# Own_RPi_Streamerboard_pro_v1_4_Final_AR.net
KiCad netlist of a schematic drawn in EAGLE
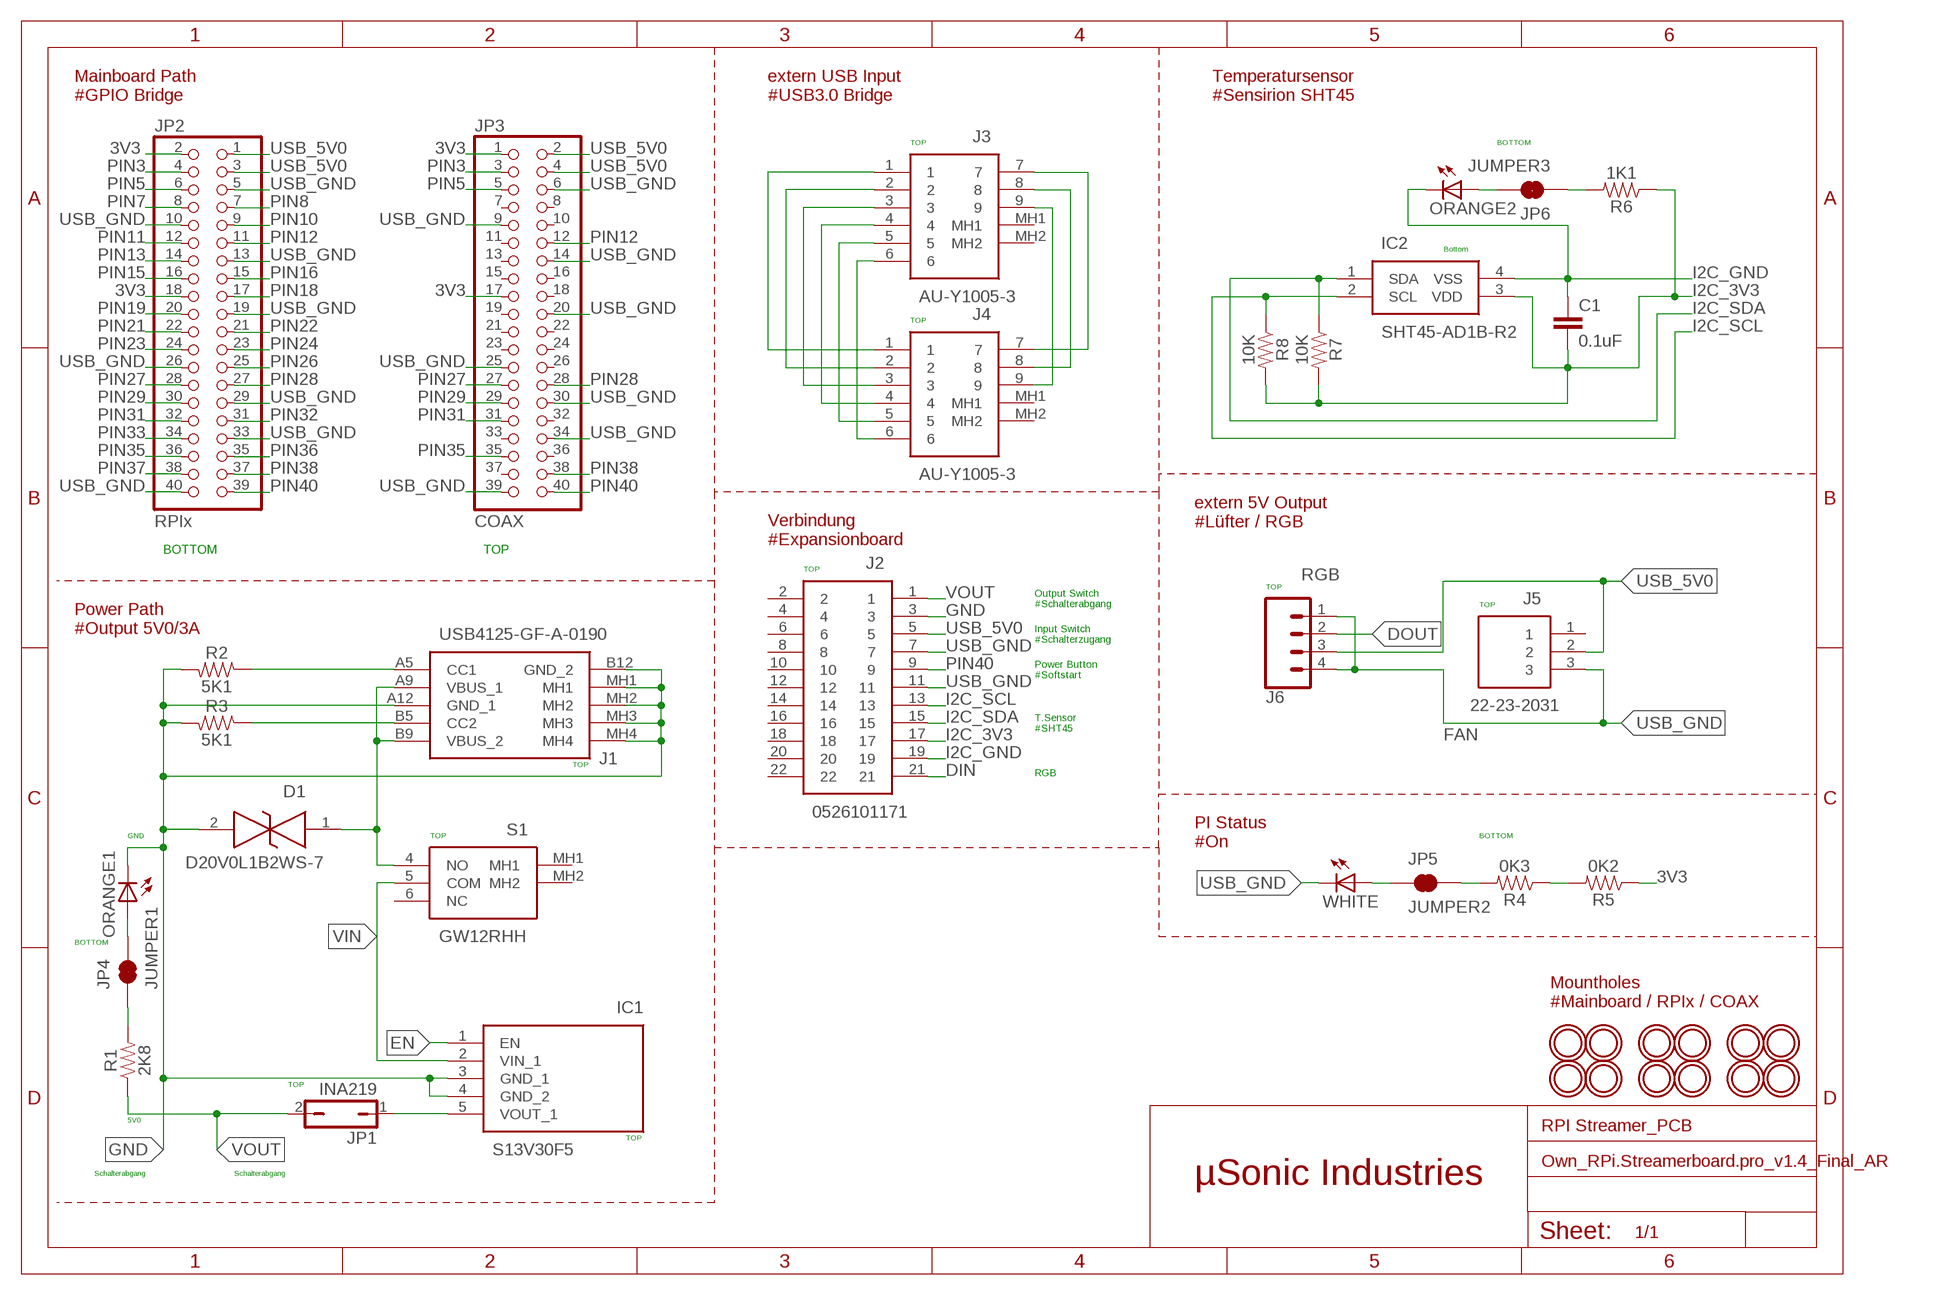
[diagram p0: schematic, sheet 1]

(export (version "E")
  (design (tool "Eeschema 10.0.6"))
  (components
    (comp (ref "C1")
      (value "0.1uF")
      (footprint "eagle-import:0805")
      (libsource (lib "eagle-import") (part "1.0UF-0805-25V-10%"))
    )
    (comp (ref "D1")
      (value "D20V0L1B2WS-7")
      (footprint "eagle-import:SOD2513X120N")
      (libsource (lib "eagle-import") (part "D20V0L1B2WS-7"))
    )
    (comp (ref "IC1")
      (value "S13V30F5")
      (footprint "eagle-import:S13V30F5")
      (libsource (lib "eagle-import") (part "S13V30F5"))
    )
    (comp (ref "IC2")
      (value "SHT45-AD1B-R2")
      (footprint "eagle-import:SHT45AD1BR2")
      (fields (field (name "MOUSER_PART_NUMBER") "403-SHT45-AD1B-R2"))
      (libsource (lib "eagle-import") (part "SHT45-AD1B-R2"))
    )
    (comp (ref "J1")
      (value "USB4125-GF-A-0190")
      (footprint "eagle-import:USB4125GFA0190")
      (fields (field (name "MOUSER_PART_NUMBER") "640-USB4125-GF-A-190"))
      (libsource (lib "eagle-import") (part "USB4125-GF-A-0190"))
    )
    (comp (ref "J2")
      (value "0526101171")
      (footprint "eagle-import:0526101171")
      (fields (field (name "ARROW_PART_NUMBER") "0526101433"))
      (libsource (lib "eagle-import") (part "0526101171"))
    )
    (comp (ref "J3")
      (value "AU-Y1005-3")
      (footprint "eagle-import:AUY10053")
      (libsource (lib "eagle-import") (part "AU-Y1005-3"))
    )
    (comp (ref "J4")
      (value "AU-Y1005-3")
      (footprint "eagle-import:AUY10053")
      (libsource (lib "eagle-import") (part "AU-Y1005-3"))
    )
    (comp (ref "J5")
      (value "22-23-2031")
      (footprint "eagle-import:SHDR3W82P0X254_1X3_747X635X818")
      (fields (field (name "MOUSER_PART_NUMBER") "538-22-23-2031"))
      (libsource (lib "eagle-import") (part "22-23-2031"))
    )
    (comp (ref "J6")
      (value "CONN_041X04_NO_SILK")
      (footprint "eagle-import:1X04_NO_SILK")
      (libsource (lib "eagle-import") (part "CONN_041X04_NO_SILK"))
    )
    (comp (ref "JP1")
      (value "INA219")
      (footprint "eagle-import:1X02_NO_SILK")
      (libsource (lib "eagle-import") (part "JP1Q2JP2"))
    )
    (comp (ref "JP2")
      (value "RPIx")
      (footprint "eagle-import:2X20-BIG")
      (libsource (lib "eagle-import") (part "PINHD-2X20-BIG"))
    )
    (comp (ref "JP3")
      (value "COAX")
      (footprint "eagle-import:2X20-BIG")
      (libsource (lib "eagle-import") (part "PINHD-2X20-BIG"))
    )
    (comp (ref "JP4")
      (value "JUMPER1")
      (footprint "eagle-import:SMT-JUMPER_2_NC_TRACE_SILK")
      (libsource (lib "eagle-import") (part "JUMPER-SMT_2_NC_TRACE_SILK"))
    )
    (comp (ref "JP5")
      (value "JUMPER2")
      (footprint "eagle-import:SMT-JUMPER_2_NC_TRACE_SILK")
      (libsource (lib "eagle-import") (part "JUMPER-SMT_2_NC_TRACE_SILK"))
    )
    (comp (ref "JP6")
      (value "JUMPER3")
      (footprint "eagle-import:SMT-JUMPER_2_NC_TRACE_SILK")
      (libsource (lib "eagle-import") (part "JUMPER-SMT_2_NC_TRACE_SILK"))
    )
    (comp (ref "ORANGE1")
      (value "LEDCHIPLED_0805")
      (footprint "eagle-import:CHIPLED_0805")
      (libsource (lib "eagle-import") (part "LEDCHIPLED_0805"))
    )
    (comp (ref "ORANGE2")
      (value "LEDCHIPLED_0805")
      (footprint "eagle-import:CHIPLED_0805")
      (libsource (lib "eagle-import") (part "LEDCHIPLED_0805"))
    )
    (comp (ref "R1")
      (value "2K8")
      (footprint "eagle-import:0805")
      (libsource (lib "eagle-import") (part "RESISTOR0805"))
    )
    (comp (ref "R2")
      (value "5K1")
      (footprint "eagle-import:0805")
      (libsource (lib "eagle-import") (part "RESISTOR0805"))
    )
    (comp (ref "R3")
      (value "5K1")
      (footprint "eagle-import:0805")
      (libsource (lib "eagle-import") (part "RESISTOR0805"))
    )
    (comp (ref "R4")
      (value "0K3")
      (footprint "eagle-import:0805")
      (libsource (lib "eagle-import") (part "RESISTOR0805"))
    )
    (comp (ref "R5")
      (value "0K2")
      (footprint "eagle-import:0805")
      (libsource (lib "eagle-import") (part "RESISTOR0805"))
    )
    (comp (ref "R6")
      (value "1K1")
      (footprint "eagle-import:0805")
      (libsource (lib "eagle-import") (part "RESISTOR0805"))
    )
    (comp (ref "R7")
      (value "10K")
      (footprint "eagle-import:0805")
      (libsource (lib "eagle-import") (part "RESISTOR0805"))
    )
    (comp (ref "R8")
      (value "10K")
      (footprint "eagle-import:0805")
      (libsource (lib "eagle-import") (part "RESISTOR0805"))
    )
    (comp (ref "S1")
      (value "GW12RHH")
      (footprint "eagle-import:GW12RHH")
      (fields (field (name "MOUSER_PART_NUMBER") "633-GW12RHH"))
      (libsource (lib "eagle-import") (part "GW12RHH"))
    )
    (comp (ref "U$4")
      (value "MOUNTINGHOLE2.5")
      (footprint "eagle-import:MOUNTINGHOLE_2.5_PLATED")
      (libsource (lib "eagle-import") (part "MOUNTINGHOLE2.5"))
    )
    (comp (ref "U$5")
      (value "MOUNTINGHOLE2.5")
      (footprint "eagle-import:MOUNTINGHOLE_2.5_PLATED")
      (libsource (lib "eagle-import") (part "MOUNTINGHOLE2.5"))
    )
    (comp (ref "U$6")
      (value "MOUNTINGHOLE2.5")
      (footprint "eagle-import:MOUNTINGHOLE_2.5_PLATED")
      (libsource (lib "eagle-import") (part "MOUNTINGHOLE2.5"))
    )
    (comp (ref "U$7")
      (value "MOUNTINGHOLE2.5")
      (footprint "eagle-import:MOUNTINGHOLE_2.5_PLATED")
      (libsource (lib "eagle-import") (part "MOUNTINGHOLE2.5"))
    )
    (comp (ref "U$8")
      (value "MOUNTINGHOLE2.5")
      (footprint "eagle-import:MOUNTINGHOLE_2.5_PLATED")
      (libsource (lib "eagle-import") (part "MOUNTINGHOLE2.5"))
    )
    (comp (ref "U$10")
      (value "MOUNTINGHOLE2.5")
      (footprint "eagle-import:MOUNTINGHOLE_2.5_PLATED")
      (libsource (lib "eagle-import") (part "MOUNTINGHOLE2.5"))
    )
    (comp (ref "U$11")
      (value "MOUNTINGHOLE2.5")
      (footprint "eagle-import:MOUNTINGHOLE_2.5_PLATED")
      (libsource (lib "eagle-import") (part "MOUNTINGHOLE2.5"))
    )
    (comp (ref "U$13")
      (value "MOUNTINGHOLE2.5")
      (footprint "eagle-import:MOUNTINGHOLE_2.5_PLATED")
      (libsource (lib "eagle-import") (part "MOUNTINGHOLE2.5"))
    )
    (comp (ref "U$14")
      (value "MOUNTINGHOLE2.5")
      (footprint "eagle-import:MOUNTINGHOLE_2.5_PLATED")
      (libsource (lib "eagle-import") (part "MOUNTINGHOLE2.5"))
    )
    (comp (ref "U$15")
      (value "MOUNTINGHOLE2.5")
      (footprint "eagle-import:MOUNTINGHOLE_2.5_PLATED")
      (libsource (lib "eagle-import") (part "MOUNTINGHOLE2.5"))
    )
    (comp (ref "U$16")
      (value "MOUNTINGHOLE2.5")
      (footprint "eagle-import:MOUNTINGHOLE_2.5_PLATED")
      (libsource (lib "eagle-import") (part "MOUNTINGHOLE2.5"))
    )
    (comp (ref "U$17")
      (value "MOUNTINGHOLE2.5")
      (footprint "eagle-import:MOUNTINGHOLE_2.5_PLATED")
      (libsource (lib "eagle-import") (part "MOUNTINGHOLE2.5"))
    )
    (comp (ref "WHITE")
      (value "LEDCHIPLED_0805")
      (footprint "eagle-import:CHIPLED_0805")
      (libsource (lib "eagle-import") (part "LEDCHIPLED_0805"))
    )
  )
  (nets
    (net (code "1") (name "/3V3") (class "Default")
      (node (ref "JP2") (pin "18") (pinfunction "18_18") (pintype "passive"))
      (node (ref "JP2") (pin "2") (pinfunction "2_2") (pintype "passive"))
      (node (ref "JP3") (pin "1") (pinfunction "1_1") (pintype "passive"))
      (node (ref "JP3") (pin "17") (pinfunction "17_17") (pintype "passive"))
      (node (ref "R5") (pin "1") (pinfunction "1_1") (pintype "passive"))
    )
    (net (code "2") (name "/DIN") (class "Default")
      (node (ref "J2") (pin "21") (pinfunction "21_21") (pintype "bidirectional"))
    )
    (net (code "3") (name "/I2C_3V3") (class "Default")
      (node (ref "C1") (pin "2") (pinfunction "2_2") (pintype "passive"))
      (node (ref "IC2") (pin "3") (pinfunction "VDD_3") (pintype "bidirectional"))
      (node (ref "J2") (pin "17") (pinfunction "17_17") (pintype "bidirectional"))
      (node (ref "R6") (pin "1") (pinfunction "1_1") (pintype "passive"))
      (node (ref "R7") (pin "2") (pinfunction "2_2") (pintype "passive"))
      (node (ref "R8") (pin "2") (pinfunction "2_2") (pintype "passive"))
    )
    (net (code "4") (name "/I2C_GND") (class "Default")
      (node (ref "C1") (pin "1") (pinfunction "1_1") (pintype "passive"))
      (node (ref "IC2") (pin "4") (pinfunction "VSS_4") (pintype "bidirectional"))
      (node (ref "J2") (pin "19") (pinfunction "19_19") (pintype "bidirectional"))
      (node (ref "ORANGE2") (pin "C") (pinfunction "C_C") (pintype "passive"))
    )
    (net (code "5") (name "/I2C_SCL") (class "Default")
      (node (ref "IC2") (pin "2") (pinfunction "SCL_2") (pintype "bidirectional"))
      (node (ref "J2") (pin "13") (pinfunction "13_13") (pintype "bidirectional"))
      (node (ref "R8") (pin "1") (pinfunction "1_1") (pintype "passive"))
    )
    (net (code "6") (name "/I2C_SDA") (class "Default")
      (node (ref "IC2") (pin "1") (pinfunction "SDA_1") (pintype "bidirectional"))
      (node (ref "J2") (pin "15") (pinfunction "15_15") (pintype "bidirectional"))
      (node (ref "R7") (pin "1") (pinfunction "1_1") (pintype "passive"))
    )
    (net (code "7") (name "/PIN3") (class "Default")
      (node (ref "JP2") (pin "4") (pinfunction "4_4") (pintype "passive"))
      (node (ref "JP3") (pin "3") (pinfunction "3_3") (pintype "passive"))
    )
    (net (code "8") (name "/PIN5") (class "Default")
      (node (ref "JP2") (pin "6") (pinfunction "6_6") (pintype "passive"))
      (node (ref "JP3") (pin "5") (pinfunction "5_5") (pintype "passive"))
    )
    (net (code "9") (name "/PIN7") (class "Default")
      (node (ref "JP2") (pin "8") (pinfunction "8_8") (pintype "passive"))
    )
    (net (code "10") (name "/PIN8") (class "Default")
      (node (ref "JP2") (pin "7") (pinfunction "7_7") (pintype "passive"))
    )
    (net (code "11") (name "/PIN10") (class "Default")
      (node (ref "JP2") (pin "9") (pinfunction "9_9") (pintype "passive"))
    )
    (net (code "12") (name "/PIN11") (class "Default")
      (node (ref "JP2") (pin "12") (pinfunction "12_12") (pintype "passive"))
    )
    (net (code "13") (name "/PIN12") (class "Default")
      (node (ref "JP2") (pin "11") (pinfunction "11_11") (pintype "passive"))
      (node (ref "JP3") (pin "12") (pinfunction "12_12") (pintype "passive"))
    )
    (net (code "14") (name "/PIN13") (class "Default")
      (node (ref "JP2") (pin "14") (pinfunction "14_14") (pintype "passive"))
    )
    (net (code "15") (name "/PIN15") (class "Default")
      (node (ref "JP2") (pin "16") (pinfunction "16_16") (pintype "passive"))
    )
    (net (code "16") (name "/PIN16") (class "Default")
      (node (ref "JP2") (pin "15") (pinfunction "15_15") (pintype "passive"))
    )
    (net (code "17") (name "/PIN18") (class "Default")
      (node (ref "JP2") (pin "17") (pinfunction "17_17") (pintype "passive"))
    )
    (net (code "18") (name "/PIN19") (class "Default")
      (node (ref "JP2") (pin "20") (pinfunction "20_20") (pintype "passive"))
    )
    (net (code "19") (name "/PIN21") (class "Default")
      (node (ref "JP2") (pin "22") (pinfunction "22_22") (pintype "passive"))
    )
    (net (code "20") (name "/PIN22") (class "Default")
      (node (ref "JP2") (pin "21") (pinfunction "21_21") (pintype "passive"))
    )
    (net (code "21") (name "/PIN23") (class "Default")
      (node (ref "JP2") (pin "24") (pinfunction "24_24") (pintype "passive"))
    )
    (net (code "22") (name "/PIN24") (class "Default")
      (node (ref "JP2") (pin "23") (pinfunction "23_23") (pintype "passive"))
    )
    (net (code "23") (name "/PIN26") (class "Default")
      (node (ref "JP2") (pin "25") (pinfunction "25_25") (pintype "passive"))
    )
    (net (code "24") (name "/PIN27") (class "Default")
      (node (ref "JP2") (pin "28") (pinfunction "28_28") (pintype "passive"))
      (node (ref "JP3") (pin "27") (pinfunction "27_27") (pintype "passive"))
    )
    (net (code "25") (name "/PIN28") (class "Default")
      (node (ref "JP2") (pin "27") (pinfunction "27_27") (pintype "passive"))
      (node (ref "JP3") (pin "28") (pinfunction "28_28") (pintype "passive"))
    )
    (net (code "26") (name "/PIN29") (class "Default")
      (node (ref "JP2") (pin "30") (pinfunction "30_30") (pintype "passive"))
      (node (ref "JP3") (pin "29") (pinfunction "29_29") (pintype "passive"))
    )
    (net (code "27") (name "/PIN31") (class "Default")
      (node (ref "JP2") (pin "32") (pinfunction "32_32") (pintype "passive"))
      (node (ref "JP3") (pin "31") (pinfunction "31_31") (pintype "passive"))
    )
    (net (code "28") (name "/PIN32") (class "Default")
      (node (ref "JP2") (pin "31") (pinfunction "31_31") (pintype "passive"))
    )
    (net (code "29") (name "/PIN33") (class "Default")
      (node (ref "JP2") (pin "34") (pinfunction "34_34") (pintype "passive"))
    )
    (net (code "30") (name "/PIN35") (class "Default")
      (node (ref "JP2") (pin "36") (pinfunction "36_36") (pintype "passive"))
      (node (ref "JP3") (pin "35") (pinfunction "35_35") (pintype "passive"))
    )
    (net (code "31") (name "/PIN36") (class "Default")
      (node (ref "JP2") (pin "35") (pinfunction "35_35") (pintype "passive"))
    )
    (net (code "32") (name "/PIN37") (class "Default")
      (node (ref "JP2") (pin "38") (pinfunction "38_38") (pintype "passive"))
    )
    (net (code "33") (name "/PIN38") (class "Default")
      (node (ref "JP2") (pin "37") (pinfunction "37_37") (pintype "passive"))
      (node (ref "JP3") (pin "38") (pinfunction "38_38") (pintype "passive"))
    )
    (net (code "34") (name "/PIN40") (class "Default")
      (node (ref "J2") (pin "9") (pinfunction "9_9") (pintype "bidirectional"))
      (node (ref "JP2") (pin "39") (pinfunction "39_39") (pintype "passive"))
      (node (ref "JP3") (pin "40") (pinfunction "40_40") (pintype "passive"))
    )
    (net (code "35") (name "DOUT") (class "Default")
      (node (ref "J6") (pin "2") (pinfunction "2_2") (pintype "passive"))
    )
    (net (code "36") (name "EN") (class "Default")
      (node (ref "IC1") (pin "1") (pinfunction "EN_1") (pintype "bidirectional"))
    )
    (net (code "37") (name "GND") (class "Default")
      (node (ref "D1") (pin "2") (pinfunction "2_2") (pintype "bidirectional"))
      (node (ref "IC1") (pin "3") (pinfunction "GND_1_3") (pintype "bidirectional"))
      (node (ref "IC1") (pin "4") (pinfunction "GND_2_4") (pintype "bidirectional"))
      (node (ref "J1") (pin "A12") (pinfunction "GND_1_A12") (pintype "bidirectional"))
      (node (ref "J1") (pin "B12") (pinfunction "GND_2_B12") (pintype "bidirectional"))
      (node (ref "J1") (pin "MH1") (pinfunction "MH1_MH1") (pintype "bidirectional"))
      (node (ref "J1") (pin "MH2") (pinfunction "MH2_MH2") (pintype "bidirectional"))
      (node (ref "J1") (pin "MH3") (pinfunction "MH3_MH3") (pintype "bidirectional"))
      (node (ref "J1") (pin "MH4") (pinfunction "MH4_MH4") (pintype "bidirectional"))
      (node (ref "J2") (pin "3") (pinfunction "3_3") (pintype "bidirectional"))
      (node (ref "ORANGE1") (pin "C") (pinfunction "C_C") (pintype "passive"))
      (node (ref "R2") (pin "2") (pinfunction "2_2") (pintype "passive"))
      (node (ref "R3") (pin "2") (pinfunction "2_2") (pintype "passive"))
    )
    (net (code "38") (name "Net-(IC1-VOUT_1)") (class "Default")
      (node (ref "IC1") (pin "5") (pinfunction "VOUT_1_5") (pintype "bidirectional"))
      (node (ref "JP1") (pin "1") (pinfunction "1_1") (pintype "passive"))
    )
    (net (code "39") (name "Net-(J1-CC1)") (class "Default")
      (node (ref "J1") (pin "A5") (pinfunction "CC1_A5") (pintype "bidirectional"))
      (node (ref "R2") (pin "1") (pinfunction "1_1") (pintype "passive"))
    )
    (net (code "40") (name "Net-(J1-CC2)") (class "Default")
      (node (ref "J1") (pin "B5") (pinfunction "CC2_B5") (pintype "bidirectional"))
      (node (ref "R3") (pin "1") (pinfunction "1_1") (pintype "passive"))
    )
    (net (code "41") (name "Net-(J1-VBUS_1)") (class "Default")
      (node (ref "D1") (pin "1") (pinfunction "1_1") (pintype "bidirectional"))
      (node (ref "J1") (pin "A9") (pinfunction "VBUS_1_A9") (pintype "bidirectional"))
      (node (ref "J1") (pin "B9") (pinfunction "VBUS_2_B9") (pintype "bidirectional"))
      (node (ref "S1") (pin "4") (pinfunction "NO_4") (pintype "bidirectional"))
    )
    (net (code "42") (name "Net-(J3-Pad1)") (class "Default")
      (node (ref "J3") (pin "1") (pinfunction "1_1") (pintype "bidirectional"))
      (node (ref "J4") (pin "1") (pinfunction "1_1") (pintype "bidirectional"))
    )
    (net (code "43") (name "Net-(J3-Pad2)") (class "Default")
      (node (ref "J3") (pin "2") (pinfunction "2_2") (pintype "bidirectional"))
      (node (ref "J4") (pin "2") (pinfunction "2_2") (pintype "bidirectional"))
    )
    (net (code "44") (name "Net-(J3-Pad3)") (class "Default")
      (node (ref "J3") (pin "3") (pinfunction "3_3") (pintype "bidirectional"))
      (node (ref "J4") (pin "3") (pinfunction "3_3") (pintype "bidirectional"))
    )
    (net (code "45") (name "Net-(J3-Pad4)") (class "Default")
      (node (ref "J3") (pin "4") (pinfunction "4_4") (pintype "bidirectional"))
      (node (ref "J4") (pin "4") (pinfunction "4_4") (pintype "bidirectional"))
    )
    (net (code "46") (name "Net-(J3-Pad5)") (class "Default")
      (node (ref "J3") (pin "5") (pinfunction "5_5") (pintype "bidirectional"))
      (node (ref "J4") (pin "5") (pinfunction "5_5") (pintype "bidirectional"))
    )
    (net (code "47") (name "Net-(J3-Pad6)") (class "Default")
      (node (ref "J3") (pin "6") (pinfunction "6_6") (pintype "bidirectional"))
      (node (ref "J4") (pin "6") (pinfunction "6_6") (pintype "bidirectional"))
    )
    (net (code "48") (name "Net-(J3-Pad7)") (class "Default")
      (node (ref "J3") (pin "7") (pinfunction "7_7") (pintype "bidirectional"))
      (node (ref "J4") (pin "7") (pinfunction "7_7") (pintype "bidirectional"))
    )
    (net (code "49") (name "Net-(J3-Pad8)") (class "Default")
      (node (ref "J3") (pin "8") (pinfunction "8_8") (pintype "bidirectional"))
      (node (ref "J4") (pin "8") (pinfunction "8_8") (pintype "bidirectional"))
    )
    (net (code "50") (name "Net-(J3-Pad9)") (class "Default")
      (node (ref "J3") (pin "9") (pinfunction "9_9") (pintype "bidirectional"))
      (node (ref "J4") (pin "9") (pinfunction "9_9") (pintype "bidirectional"))
    )
    (net (code "51") (name "Net-(JP4-Pad1)") (class "Default")
      (node (ref "JP4") (pin "1") (pinfunction "1_1") (pintype "passive"))
      (node (ref "R1") (pin "2") (pinfunction "2_2") (pintype "passive"))
    )
    (net (code "52") (name "Net-(JP4-Pad2)") (class "Default")
      (node (ref "JP4") (pin "2") (pinfunction "2_2") (pintype "passive"))
      (node (ref "ORANGE1") (pin "A") (pinfunction "A_A") (pintype "passive"))
    )
    (net (code "53") (name "Net-(JP5-Pad1)") (class "Default")
      (node (ref "JP5") (pin "1") (pinfunction "1_1") (pintype "passive"))
      (node (ref "WHITE") (pin "A") (pinfunction "A_A") (pintype "passive"))
    )
    (net (code "54") (name "Net-(JP5-Pad2)") (class "Default")
      (node (ref "JP5") (pin "2") (pinfunction "2_2") (pintype "passive"))
      (node (ref "R4") (pin "2") (pinfunction "2_2") (pintype "passive"))
    )
    (net (code "55") (name "Net-(JP6-Pad1)") (class "Default")
      (node (ref "JP6") (pin "1") (pinfunction "1_1") (pintype "passive"))
      (node (ref "R6") (pin "2") (pinfunction "2_2") (pintype "passive"))
    )
    (net (code "56") (name "Net-(JP6-Pad2)") (class "Default")
      (node (ref "JP6") (pin "2") (pinfunction "2_2") (pintype "passive"))
      (node (ref "ORANGE2") (pin "A") (pinfunction "A_A") (pintype "passive"))
    )
    (net (code "57") (name "Net-(R4-Pad1)") (class "Default")
      (node (ref "R4") (pin "1") (pinfunction "1_1") (pintype "passive"))
      (node (ref "R5") (pin "2") (pinfunction "2_2") (pintype "passive"))
    )
    (net (code "58") (name "USB_5V0") (class "Default")
      (node (ref "J2") (pin "5") (pinfunction "5_5") (pintype "bidirectional"))
      (node (ref "J5") (pin "2") (pinfunction "2_2") (pintype "bidirectional"))
      (node (ref "J6") (pin "3") (pinfunction "3_3") (pintype "passive"))
      (node (ref "JP2") (pin "1") (pinfunction "1_1") (pintype "passive"))
      (node (ref "JP2") (pin "3") (pinfunction "3_3") (pintype "passive"))
      (node (ref "JP3") (pin "2") (pinfunction "2_2") (pintype "passive"))
      (node (ref "JP3") (pin "4") (pinfunction "4_4") (pintype "passive"))
    )
    (net (code "59") (name "USB_GND") (class "Default")
      (node (ref "J2") (pin "11") (pinfunction "11_11") (pintype "bidirectional"))
      (node (ref "J2") (pin "7") (pinfunction "7_7") (pintype "bidirectional"))
      (node (ref "J5") (pin "3") (pinfunction "3_3") (pintype "bidirectional"))
      (node (ref "J6") (pin "1") (pinfunction "1_1") (pintype "passive"))
      (node (ref "J6") (pin "4") (pinfunction "4_4") (pintype "passive"))
      (node (ref "JP2") (pin "10") (pinfunction "10_10") (pintype "passive"))
      (node (ref "JP2") (pin "13") (pinfunction "13_13") (pintype "passive"))
      (node (ref "JP2") (pin "19") (pinfunction "19_19") (pintype "passive"))
      (node (ref "JP2") (pin "26") (pinfunction "26_26") (pintype "passive"))
      (node (ref "JP2") (pin "29") (pinfunction "29_29") (pintype "passive"))
      (node (ref "JP2") (pin "33") (pinfunction "33_33") (pintype "passive"))
      (node (ref "JP2") (pin "40") (pinfunction "40_40") (pintype "passive"))
      (node (ref "JP2") (pin "5") (pinfunction "5_5") (pintype "passive"))
      (node (ref "JP3") (pin "14") (pinfunction "14_14") (pintype "passive"))
      (node (ref "JP3") (pin "20") (pinfunction "20_20") (pintype "passive"))
      (node (ref "JP3") (pin "25") (pinfunction "25_25") (pintype "passive"))
      (node (ref "JP3") (pin "30") (pinfunction "30_30") (pintype "passive"))
      (node (ref "JP3") (pin "34") (pinfunction "34_34") (pintype "passive"))
      (node (ref "JP3") (pin "39") (pinfunction "39_39") (pintype "passive"))
      (node (ref "JP3") (pin "6") (pinfunction "6_6") (pintype "passive"))
      (node (ref "JP3") (pin "9") (pinfunction "9_9") (pintype "passive"))
      (node (ref "WHITE") (pin "C") (pinfunction "C_C") (pintype "passive"))
    )
    (net (code "60") (name "VIN") (class "Default")
      (node (ref "IC1") (pin "2") (pinfunction "VIN_1_2") (pintype "bidirectional"))
      (node (ref "S1") (pin "5") (pinfunction "COM_5") (pintype "bidirectional"))
    )
    (net (code "61") (name "VOUT") (class "Default")
      (node (ref "J2") (pin "1") (pinfunction "1_1") (pintype "bidirectional"))
      (node (ref "JP1") (pin "2") (pinfunction "2_2") (pintype "passive"))
      (node (ref "R1") (pin "1") (pinfunction "1_1") (pintype "passive"))
    )
    (net (code "62") (name "unconnected-(J2-Pad2)") (class "Default")
      (node (ref "J2") (pin "2") (pinfunction "2_2") (pintype "bidirectional"))
    )
    (net (code "63") (name "unconnected-(J2-Pad4)") (class "Default")
      (node (ref "J2") (pin "4") (pinfunction "4_4") (pintype "bidirectional"))
    )
    (net (code "64") (name "unconnected-(J2-Pad6)") (class "Default")
      (node (ref "J2") (pin "6") (pinfunction "6_6") (pintype "bidirectional"))
    )
    (net (code "65") (name "unconnected-(J2-Pad8)") (class "Default")
      (node (ref "J2") (pin "8") (pinfunction "8_8") (pintype "bidirectional"))
    )
    (net (code "66") (name "unconnected-(J2-Pad10)") (class "Default")
      (node (ref "J2") (pin "10") (pinfunction "10_10") (pintype "bidirectional"))
    )
    (net (code "67") (name "unconnected-(J2-Pad12)") (class "Default")
      (node (ref "J2") (pin "12") (pinfunction "12_12") (pintype "bidirectional"))
    )
    (net (code "68") (name "unconnected-(J2-Pad14)") (class "Default")
      (node (ref "J2") (pin "14") (pinfunction "14_14") (pintype "bidirectional"))
    )
    (net (code "69") (name "unconnected-(J2-Pad16)") (class "Default")
      (node (ref "J2") (pin "16") (pinfunction "16_16") (pintype "bidirectional"))
    )
    (net (code "70") (name "unconnected-(J2-Pad18)") (class "Default")
      (node (ref "J2") (pin "18") (pinfunction "18_18") (pintype "bidirectional"))
    )
    (net (code "71") (name "unconnected-(J2-Pad20)") (class "Default")
      (node (ref "J2") (pin "20") (pinfunction "20_20") (pintype "bidirectional"))
    )
    (net (code "72") (name "unconnected-(J2-Pad22)") (class "Default")
      (node (ref "J2") (pin "22") (pinfunction "22_22") (pintype "bidirectional"))
    )
    (net (code "73") (name "unconnected-(J3-PadMH1)") (class "Default")
      (node (ref "J3") (pin "MH1") (pinfunction "MH1_MH1") (pintype "bidirectional"))
    )
    (net (code "74") (name "unconnected-(J3-PadMH2)") (class "Default")
      (node (ref "J3") (pin "MH2") (pinfunction "MH2_MH2") (pintype "bidirectional"))
    )
    (net (code "75") (name "unconnected-(J4-PadMH1)") (class "Default")
      (node (ref "J4") (pin "MH1") (pinfunction "MH1_MH1") (pintype "bidirectional"))
    )
    (net (code "76") (name "unconnected-(J4-PadMH2)") (class "Default")
      (node (ref "J4") (pin "MH2") (pinfunction "MH2_MH2") (pintype "bidirectional"))
    )
    (net (code "77") (name "unconnected-(J5-Pad1)") (class "Default")
      (node (ref "J5") (pin "1") (pinfunction "1_1") (pintype "bidirectional"))
    )
    (net (code "78") (name "unconnected-(JP3-Pad7)") (class "Default")
      (node (ref "JP3") (pin "7") (pinfunction "7_7") (pintype "passive"))
    )
    (net (code "79") (name "unconnected-(JP3-Pad8)") (class "Default")
      (node (ref "JP3") (pin "8") (pinfunction "8_8") (pintype "passive"))
    )
    (net (code "80") (name "unconnected-(JP3-Pad10)") (class "Default")
      (node (ref "JP3") (pin "10") (pinfunction "10_10") (pintype "passive"))
    )
    (net (code "81") (name "unconnected-(JP3-Pad11)") (class "Default")
      (node (ref "JP3") (pin "11") (pinfunction "11_11") (pintype "passive"))
    )
    (net (code "82") (name "unconnected-(JP3-Pad13)") (class "Default")
      (node (ref "JP3") (pin "13") (pinfunction "13_13") (pintype "passive"))
    )
    (net (code "83") (name "unconnected-(JP3-Pad15)") (class "Default")
      (node (ref "JP3") (pin "15") (pinfunction "15_15") (pintype "passive"))
    )
    (net (code "84") (name "unconnected-(JP3-Pad16)") (class "Default")
      (node (ref "JP3") (pin "16") (pinfunction "16_16") (pintype "passive"))
    )
    (net (code "85") (name "unconnected-(JP3-Pad18)") (class "Default")
      (node (ref "JP3") (pin "18") (pinfunction "18_18") (pintype "passive"))
    )
    (net (code "86") (name "unconnected-(JP3-Pad19)") (class "Default")
      (node (ref "JP3") (pin "19") (pinfunction "19_19") (pintype "passive"))
    )
    (net (code "87") (name "unconnected-(JP3-Pad21)") (class "Default")
      (node (ref "JP3") (pin "21") (pinfunction "21_21") (pintype "passive"))
    )
    (net (code "88") (name "unconnected-(JP3-Pad22)") (class "Default")
      (node (ref "JP3") (pin "22") (pinfunction "22_22") (pintype "passive"))
    )
    (net (code "89") (name "unconnected-(JP3-Pad23)") (class "Default")
      (node (ref "JP3") (pin "23") (pinfunction "23_23") (pintype "passive"))
    )
    (net (code "90") (name "unconnected-(JP3-Pad24)") (class "Default")
      (node (ref "JP3") (pin "24") (pinfunction "24_24") (pintype "passive"))
    )
    (net (code "91") (name "unconnected-(JP3-Pad26)") (class "Default")
      (node (ref "JP3") (pin "26") (pinfunction "26_26") (pintype "passive"))
    )
    (net (code "92") (name "unconnected-(JP3-Pad32)") (class "Default")
      (node (ref "JP3") (pin "32") (pinfunction "32_32") (pintype "passive"))
    )
    (net (code "93") (name "unconnected-(JP3-Pad33)") (class "Default")
      (node (ref "JP3") (pin "33") (pinfunction "33_33") (pintype "passive"))
    )
    (net (code "94") (name "unconnected-(JP3-Pad36)") (class "Default")
      (node (ref "JP3") (pin "36") (pinfunction "36_36") (pintype "passive"))
    )
    (net (code "95") (name "unconnected-(JP3-Pad37)") (class "Default")
      (node (ref "JP3") (pin "37") (pinfunction "37_37") (pintype "passive"))
    )
    (net (code "96") (name "unconnected-(S1-NC-Pad6)") (class "Default")
      (node (ref "S1") (pin "6") (pinfunction "NC_6") (pintype "no_connect"))
    )
    (net (code "97") (name "unconnected-(S1-PadMH1)") (class "Default")
      (node (ref "S1") (pin "MH1") (pinfunction "MH1_MH1") (pintype "bidirectional"))
    )
    (net (code "98") (name "unconnected-(S1-PadMH2)") (class "Default")
      (node (ref "S1") (pin "MH2") (pinfunction "MH2_MH2") (pintype "bidirectional"))
    )
  )
)
